# Acumulator.net
KiCad netlist of a schematic drawn in EAGLE
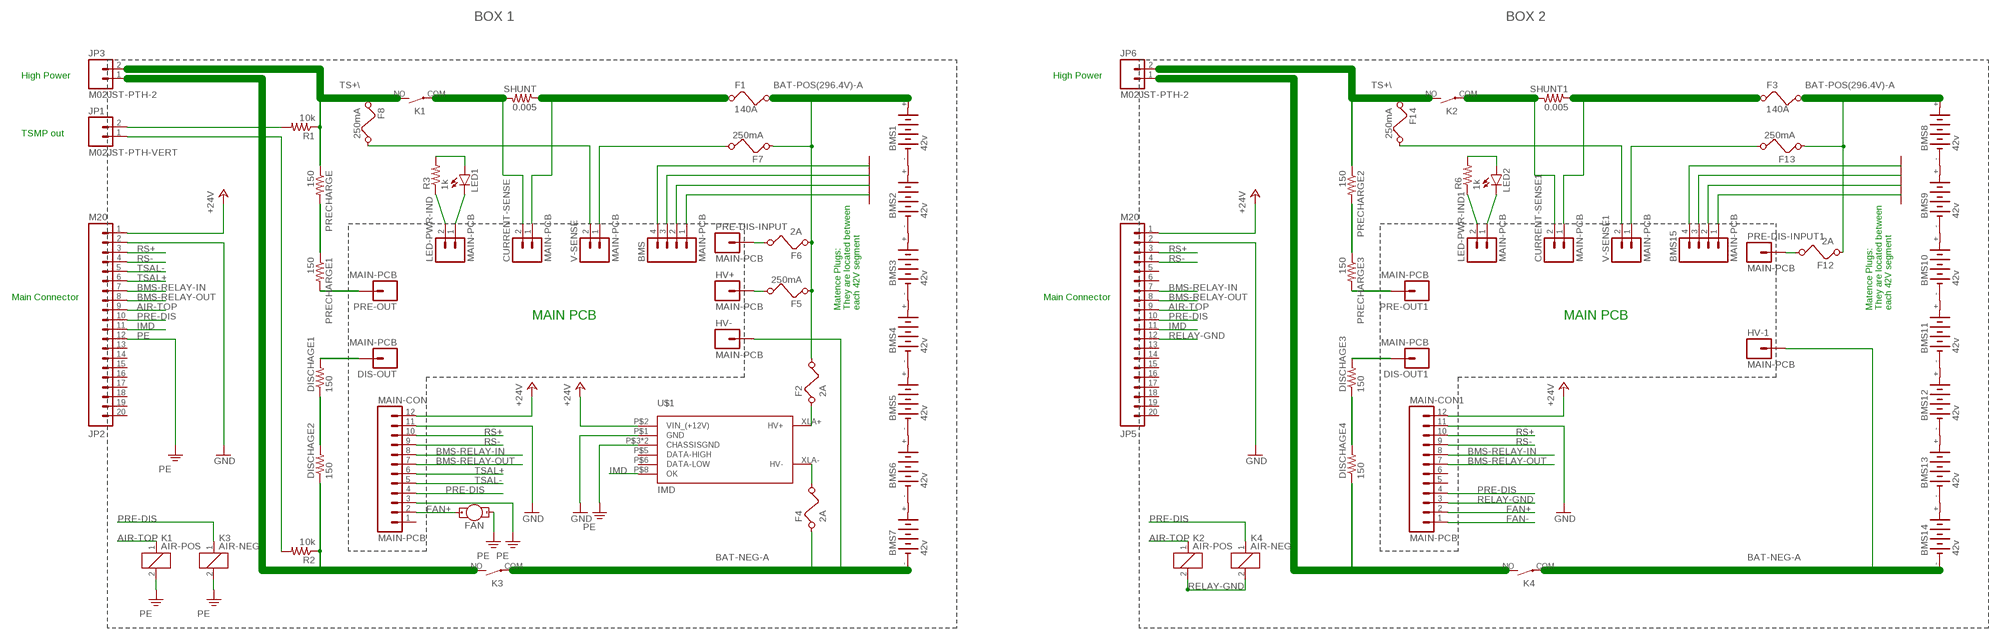
[diagram p0: schematic, sheet 1]
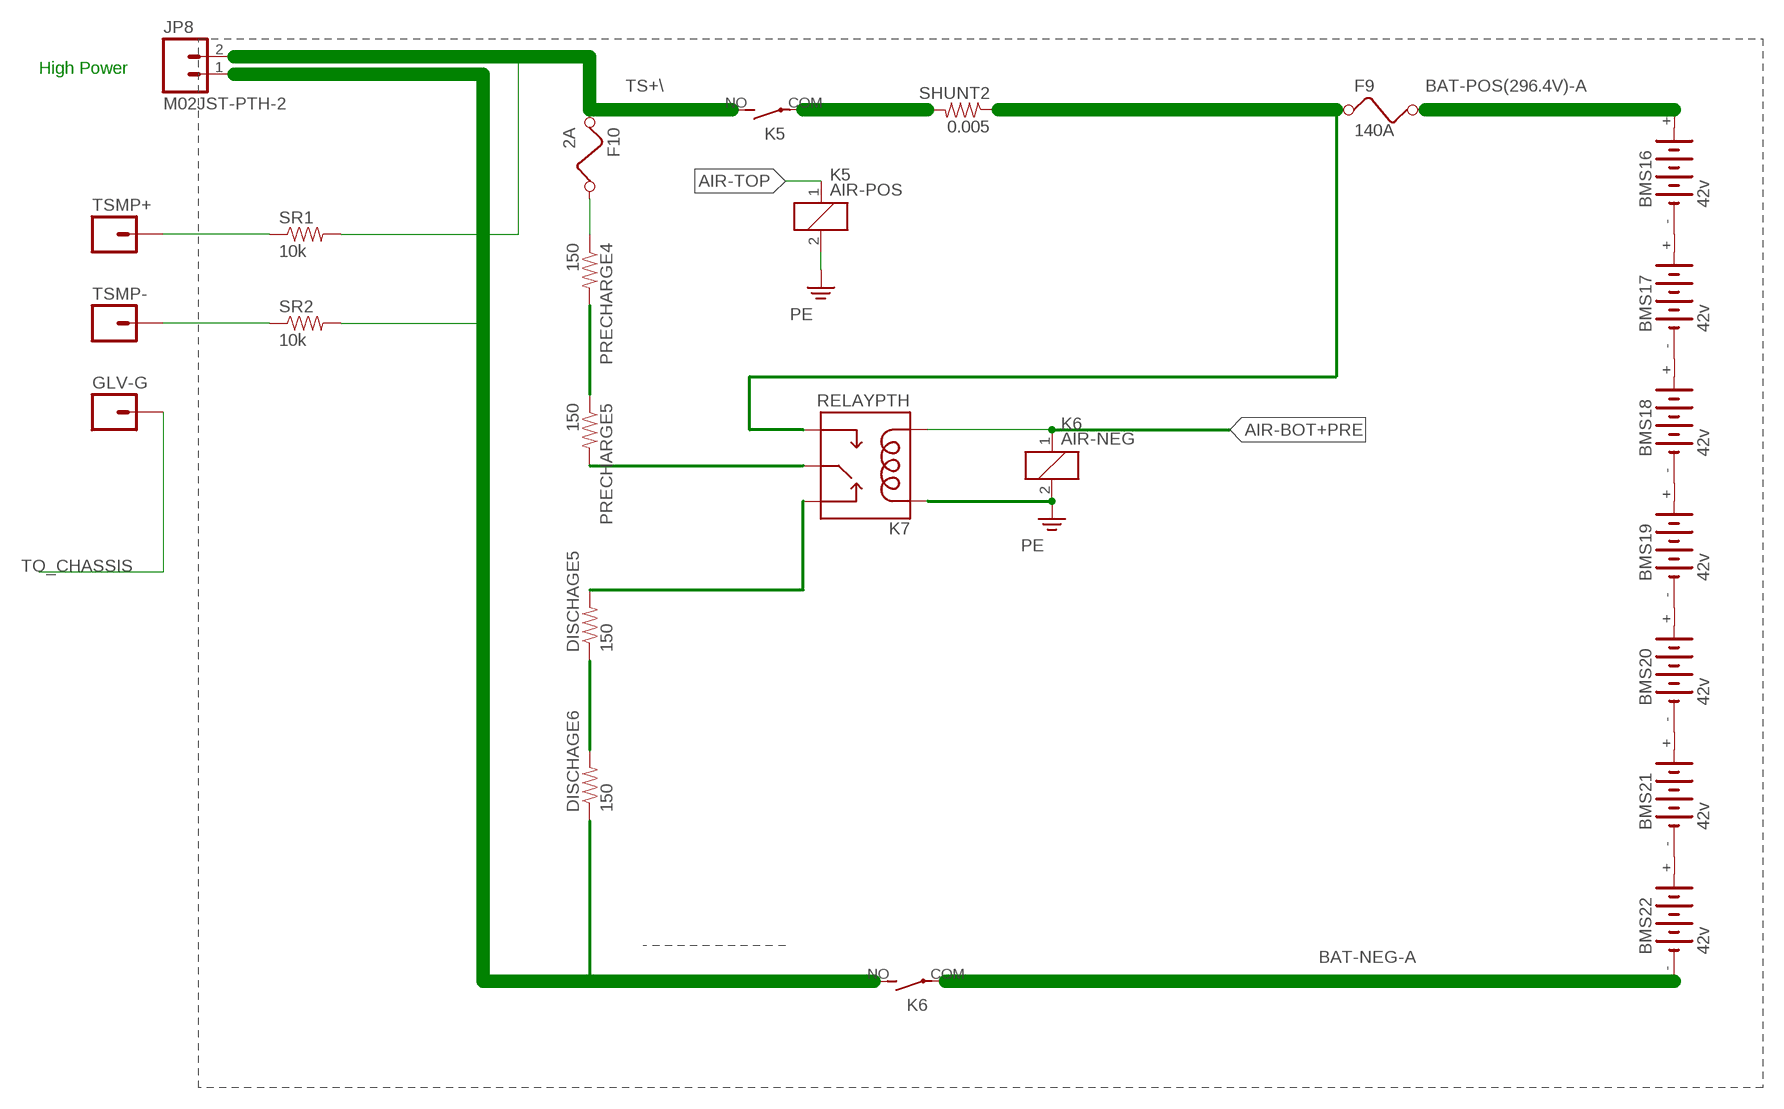
[diagram p1: schematic, sheet 2]
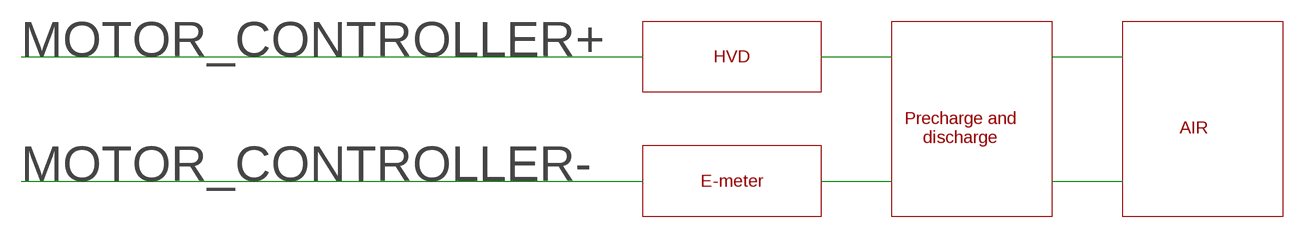
[diagram p2: schematic, sheet 3]

(export (version "E")
  (design (tool "Eeschema 10.0.6"))
  (components
    (comp (ref "BMS16")
      (value "42v")
      (footprint "eagle-import:VST4")
      (libsource (lib "eagle-import") (part "VST4V8"))
    )
    (comp (ref "BMS17")
      (value "42v")
      (footprint "eagle-import:VST4")
      (libsource (lib "eagle-import") (part "VST4V8"))
    )
    (comp (ref "BMS18")
      (value "42v")
      (footprint "eagle-import:VST4")
      (libsource (lib "eagle-import") (part "VST4V8"))
    )
    (comp (ref "BMS19")
      (value "42v")
      (footprint "eagle-import:VST4")
      (libsource (lib "eagle-import") (part "VST4V8"))
    )
    (comp (ref "BMS20")
      (value "42v")
      (footprint "eagle-import:VST4")
      (libsource (lib "eagle-import") (part "VST4V8"))
    )
    (comp (ref "BMS21")
      (value "42v")
      (footprint "eagle-import:VST4")
      (libsource (lib "eagle-import") (part "VST4V8"))
    )
    (comp (ref "BMS22")
      (value "42v")
      (footprint "eagle-import:VST4")
      (libsource (lib "eagle-import") (part "VST4V8"))
    )
    (comp (ref "DISCHAGE5")
      (value "150")
      (footprint "eagle-import:0603-RES")
      (libsource (lib "eagle-import") (part "2.0KOHM1/10W5%(0603)"))
    )
    (comp (ref "DISCHAGE6")
      (value "150")
      (footprint "eagle-import:0603-RES")
      (libsource (lib "eagle-import") (part "2.0KOHM1/10W5%(0603)"))
    )
    (comp (ref "F9")
      (value "140A")
      (footprint "eagle-import:FUSE")
      (libsource (lib "eagle-import") (part "FUSE"))
    )
    (comp (ref "F10")
      (value "2A")
      (footprint "eagle-import:FUSE")
      (libsource (lib "eagle-import") (part "FUSE"))
    )
    (comp (ref "GLV-G")
      (value "M01-SMTSO-256-ET")
      (footprint "eagle-import:SMTSO-256-ET")
      (libsource (lib "eagle-import") (part "M01-SMTSO-256-ET"))
    )
    (comp (ref "JP8")
      (value "M02JST-PTH-2")
      (footprint "eagle-import:JST-2-PTH")
      (libsource (lib "eagle-import") (part "M02JST-PTH-2"))
    )
    (comp (ref "K5")
      (value "AIR-POS")
      (footprint "eagle-import:APF30212A")
      (libsource (lib "eagle-import") (part "APF30212A"))
    )
    (comp (ref "K6")
      (value "AIR-NEG")
      (footprint "eagle-import:APF30212A")
      (libsource (lib "eagle-import") (part "APF30212A"))
    )
    (comp (ref "K7")
      (value "RELAYPTH")
      (footprint "eagle-import:RELAY-G5Q")
      (libsource (lib "eagle-import") (part "RELAYPTH"))
    )
    (comp (ref "PRECHARGE4")
      (value "150")
      (footprint "eagle-import:0603-RES")
      (libsource (lib "eagle-import") (part "2.0KOHM1/10W5%(0603)"))
    )
    (comp (ref "PRECHARGE5")
      (value "150")
      (footprint "eagle-import:0603-RES")
      (libsource (lib "eagle-import") (part "2.0KOHM1/10W5%(0603)"))
    )
    (comp (ref "SHUNT2")
      (value "0.005")
      (footprint "eagle-import:0603-RES")
      (libsource (lib "eagle-import") (part "2.0KOHM1/10W5%(0603)"))
    )
    (comp (ref "SR1")
      (value "10k")
      (footprint "eagle-import:0603-RES")
      (libsource (lib "eagle-import") (part "2.0KOHM1/10W5%(0603)"))
    )
    (comp (ref "SR2")
      (value "10k")
      (footprint "eagle-import:0603-RES")
      (libsource (lib "eagle-import") (part "2.0KOHM1/10W5%(0603)"))
    )
    (comp (ref "TSMP+")
      (value "M01-SMTSO-256-ET")
      (footprint "eagle-import:SMTSO-256-ET")
      (libsource (lib "eagle-import") (part "M01-SMTSO-256-ET"))
    )
    (comp (ref "TSMP-")
      (value "M01-SMTSO-256-ET")
      (footprint "eagle-import:SMTSO-256-ET")
      (libsource (lib "eagle-import") (part "M01-SMTSO-256-ET"))
    )
    (comp (ref "BMS")
      (value "MAIN-PCB")
      (footprint "eagle-import:1X04_LOCK_LONGPADS")
      (libsource (lib "eagle-import") (part "M04LOCK_LONGPADS"))
    )
    (comp (ref "BMS1")
      (value "42v")
      (footprint "eagle-import:VST4")
      (libsource (lib "eagle-import") (part "VST4V8"))
    )
    (comp (ref "BMS2")
      (value "42v")
      (footprint "eagle-import:VST4")
      (libsource (lib "eagle-import") (part "VST4V8"))
    )
    (comp (ref "BMS3")
      (value "42v")
      (footprint "eagle-import:VST4")
      (libsource (lib "eagle-import") (part "VST4V8"))
    )
    (comp (ref "BMS4")
      (value "42v")
      (footprint "eagle-import:VST4")
      (libsource (lib "eagle-import") (part "VST4V8"))
    )
    (comp (ref "BMS5")
      (value "42v")
      (footprint "eagle-import:VST4")
      (libsource (lib "eagle-import") (part "VST4V8"))
    )
    (comp (ref "BMS6")
      (value "42v")
      (footprint "eagle-import:VST4")
      (libsource (lib "eagle-import") (part "VST4V8"))
    )
    (comp (ref "BMS7")
      (value "42v")
      (footprint "eagle-import:VST4")
      (libsource (lib "eagle-import") (part "VST4V8"))
    )
    (comp (ref "BMS8")
      (value "42v")
      (footprint "eagle-import:VST4")
      (libsource (lib "eagle-import") (part "VST4V8"))
    )
    (comp (ref "BMS9")
      (value "42v")
      (footprint "eagle-import:VST4")
      (libsource (lib "eagle-import") (part "VST4V8"))
    )
    (comp (ref "BMS10")
      (value "42v")
      (footprint "eagle-import:VST4")
      (libsource (lib "eagle-import") (part "VST4V8"))
    )
    (comp (ref "BMS11")
      (value "42v")
      (footprint "eagle-import:VST4")
      (libsource (lib "eagle-import") (part "VST4V8"))
    )
    (comp (ref "BMS12")
      (value "42v")
      (footprint "eagle-import:VST4")
      (libsource (lib "eagle-import") (part "VST4V8"))
    )
    (comp (ref "BMS13")
      (value "42v")
      (footprint "eagle-import:VST4")
      (libsource (lib "eagle-import") (part "VST4V8"))
    )
    (comp (ref "BMS14")
      (value "42v")
      (footprint "eagle-import:VST4")
      (libsource (lib "eagle-import") (part "VST4V8"))
    )
    (comp (ref "BMS15")
      (value "MAIN-PCB")
      (footprint "eagle-import:1X04_LOCK_LONGPADS")
      (libsource (lib "eagle-import") (part "M04LOCK_LONGPADS"))
    )
    (comp (ref "CURRENT-SENSE")
      (value "MAIN-PCB")
      (footprint "eagle-import:JST-2-PTH-NS")
      (libsource (lib "eagle-import") (part "M02-JST-2-PTH-NO_SILK"))
    )
    (comp (ref "CURRENT-SENSE1")
      (value "MAIN-PCB")
      (footprint "eagle-import:JST-2-PTH-NS")
      (libsource (lib "eagle-import") (part "M02-JST-2-PTH-NO_SILK"))
    )
    (comp (ref "DIS-OUT")
      (value "MAIN-PCB")
      (footprint "eagle-import:1X01_OFFSET")
      (libsource (lib "eagle-import") (part "M01OFFSET"))
    )
    (comp (ref "DIS-OUT1")
      (value "MAIN-PCB")
      (footprint "eagle-import:1X01_OFFSET")
      (libsource (lib "eagle-import") (part "M01OFFSET"))
    )
    (comp (ref "DISCHAGE1")
      (value "150")
      (footprint "eagle-import:0603-RES")
      (libsource (lib "eagle-import") (part "2.0KOHM1/10W5%(0603)"))
    )
    (comp (ref "DISCHAGE2")
      (value "150")
      (footprint "eagle-import:0603-RES")
      (libsource (lib "eagle-import") (part "2.0KOHM1/10W5%(0603)"))
    )
    (comp (ref "DISCHAGE3")
      (value "150")
      (footprint "eagle-import:0603-RES")
      (libsource (lib "eagle-import") (part "2.0KOHM1/10W5%(0603)"))
    )
    (comp (ref "DISCHAGE4")
      (value "150")
      (footprint "eagle-import:0603-RES")
      (libsource (lib "eagle-import") (part "2.0KOHM1/10W5%(0603)"))
    )
    (comp (ref "F1")
      (value "140A")
      (footprint "eagle-import:FUSE")
      (libsource (lib "eagle-import") (part "FUSE"))
    )
    (comp (ref "F2")
      (value "2A")
      (footprint "eagle-import:FUSE")
      (libsource (lib "eagle-import") (part "FUSE"))
    )
    (comp (ref "F3")
      (value "140A")
      (footprint "eagle-import:FUSE")
      (libsource (lib "eagle-import") (part "FUSE"))
    )
    (comp (ref "F4")
      (value "2A")
      (footprint "eagle-import:FUSE")
      (libsource (lib "eagle-import") (part "FUSE"))
    )
    (comp (ref "F5")
      (value "250mA")
      (footprint "eagle-import:FUSE")
      (libsource (lib "eagle-import") (part "FUSE"))
    )
    (comp (ref "F6")
      (value "2A")
      (footprint "eagle-import:FUSE")
      (libsource (lib "eagle-import") (part "FUSE"))
    )
    (comp (ref "F7")
      (value "250mA")
      (footprint "eagle-import:FUSE")
      (libsource (lib "eagle-import") (part "FUSE"))
    )
    (comp (ref "F8")
      (value "250mA")
      (footprint "eagle-import:FUSE")
      (libsource (lib "eagle-import") (part "FUSE"))
    )
    (comp (ref "F12")
      (value "2A")
      (footprint "eagle-import:FUSE")
      (libsource (lib "eagle-import") (part "FUSE"))
    )
    (comp (ref "F13")
      (value "250mA")
      (footprint "eagle-import:FUSE")
      (libsource (lib "eagle-import") (part "FUSE"))
    )
    (comp (ref "F14")
      (value "250mA")
      (footprint "eagle-import:FUSE")
      (libsource (lib "eagle-import") (part "FUSE"))
    )
    (comp (ref "FAN")
      (value "MOTOR10MM")
      (footprint "eagle-import:VIBE-MOTOR-10MM")
      (libsource (lib "eagle-import") (part "MOTOR10MM"))
    )
    (comp (ref "HV+")
      (value "MAIN-PCB")
      (footprint "eagle-import:1X01_OFFSET")
      (libsource (lib "eagle-import") (part "M01OFFSET"))
    )
    (comp (ref "HV-")
      (value "MAIN-PCB")
      (footprint "eagle-import:1X01_OFFSET")
      (libsource (lib "eagle-import") (part "M01OFFSET"))
    )
    (comp (ref "HV-1")
      (value "MAIN-PCB")
      (footprint "eagle-import:1X01_OFFSET")
      (libsource (lib "eagle-import") (part "M01OFFSET"))
    )
    (comp (ref "JP1")
      (value "M02JST-PTH-VERT")
      (footprint "eagle-import:JST-2-PTH-VERT")
      (libsource (lib "eagle-import") (part "M02JST-PTH-VERT"))
    )
    (comp (ref "JP2")
      (value "M20")
      (footprint "eagle-import:1X20")
      (libsource (lib "eagle-import") (part "M20"))
    )
    (comp (ref "JP3")
      (value "M02JST-PTH-2")
      (footprint "eagle-import:JST-2-PTH")
      (libsource (lib "eagle-import") (part "M02JST-PTH-2"))
    )
    (comp (ref "JP5")
      (value "M20")
      (footprint "eagle-import:1X20")
      (libsource (lib "eagle-import") (part "M20"))
    )
    (comp (ref "JP6")
      (value "M02JST-PTH-2")
      (footprint "eagle-import:JST-2-PTH")
      (libsource (lib "eagle-import") (part "M02JST-PTH-2"))
    )
    (comp (ref "K1")
      (value "AIR-POS")
      (footprint "eagle-import:APF30212A")
      (libsource (lib "eagle-import") (part "APF30212A"))
    )
    (comp (ref "K2")
      (value "AIR-POS")
      (footprint "eagle-import:APF30212A")
      (libsource (lib "eagle-import") (part "APF30212A"))
    )
    (comp (ref "K3")
      (value "AIR-NEG")
      (footprint "eagle-import:APF30212A")
      (libsource (lib "eagle-import") (part "APF30212A"))
    )
    (comp (ref "K4")
      (value "AIR-NEG")
      (footprint "eagle-import:APF30212A")
      (libsource (lib "eagle-import") (part "APF30212A"))
    )
    (comp (ref "LED-PWR-IND")
      (value "MAIN-PCB")
      (footprint "eagle-import:JST-2-PTH-NS")
      (libsource (lib "eagle-import") (part "M02-JST-2-PTH-NO_SILK"))
    )
    (comp (ref "LED-PWR-IND1")
      (value "MAIN-PCB")
      (footprint "eagle-import:JST-2-PTH-NS")
      (libsource (lib "eagle-import") (part "M02-JST-2-PTH-NO_SILK"))
    )
    (comp (ref "LED1")
      (value "LED5MM")
      (footprint "eagle-import:LED5MM")
      (libsource (lib "eagle-import") (part "LED5MM"))
    )
    (comp (ref "LED2")
      (value "LED5MM")
      (footprint "eagle-import:LED5MM")
      (libsource (lib "eagle-import") (part "LED5MM"))
    )
    (comp (ref "MAIN-CON")
      (value "MAIN-PCB")
      (footprint "eagle-import:1X12_LOCK")
      (libsource (lib "eagle-import") (part "M12LOCK"))
    )
    (comp (ref "MAIN-CON1")
      (value "MAIN-PCB")
      (footprint "eagle-import:1X12_LOCK")
      (libsource (lib "eagle-import") (part "M12LOCK"))
    )
    (comp (ref "PRE-DIS-INPUT")
      (value "MAIN-PCB")
      (footprint "eagle-import:1X01_OFFSET")
      (libsource (lib "eagle-import") (part "M01OFFSET"))
    )
    (comp (ref "PRE-DIS-INPUT1")
      (value "MAIN-PCB")
      (footprint "eagle-import:1X01_OFFSET")
      (libsource (lib "eagle-import") (part "M01OFFSET"))
    )
    (comp (ref "PRE-OUT")
      (value "MAIN-PCB")
      (footprint "eagle-import:1X01_OFFSET")
      (libsource (lib "eagle-import") (part "M01OFFSET"))
    )
    (comp (ref "PRE-OUT1")
      (value "MAIN-PCB")
      (footprint "eagle-import:1X01_OFFSET")
      (libsource (lib "eagle-import") (part "M01OFFSET"))
    )
    (comp (ref "PRECHARGE")
      (value "150")
      (footprint "eagle-import:0603-RES")
      (libsource (lib "eagle-import") (part "2.0KOHM1/10W5%(0603)"))
    )
    (comp (ref "PRECHARGE1")
      (value "150")
      (footprint "eagle-import:0603-RES")
      (libsource (lib "eagle-import") (part "2.0KOHM1/10W5%(0603)"))
    )
    (comp (ref "PRECHARGE2")
      (value "150")
      (footprint "eagle-import:0603-RES")
      (libsource (lib "eagle-import") (part "2.0KOHM1/10W5%(0603)"))
    )
    (comp (ref "PRECHARGE3")
      (value "150")
      (footprint "eagle-import:0603-RES")
      (libsource (lib "eagle-import") (part "2.0KOHM1/10W5%(0603)"))
    )
    (comp (ref "R1")
      (value "10k")
      (footprint "eagle-import:0805")
      (libsource (lib "eagle-import") (part "RESISTOR0805-RES"))
    )
    (comp (ref "R2")
      (value "10k")
      (footprint "eagle-import:0805")
      (libsource (lib "eagle-import") (part "RESISTOR0805-RES"))
    )
    (comp (ref "R3")
      (value "1k")
      (footprint "eagle-import:0603-RES")
      (libsource (lib "eagle-import") (part "2.0KOHM1/10W5%(0603)"))
    )
    (comp (ref "R6")
      (value "1k")
      (footprint "eagle-import:0603-RES")
      (libsource (lib "eagle-import") (part "2.0KOHM1/10W5%(0603)"))
    )
    (comp (ref "SHUNT")
      (value "0.005")
      (footprint "eagle-import:0603-RES")
      (libsource (lib "eagle-import") (part "2.0KOHM1/10W5%(0603)"))
    )
    (comp (ref "SHUNT1")
      (value "0.005")
      (footprint "eagle-import:0603-RES")
      (libsource (lib "eagle-import") (part "2.0KOHM1/10W5%(0603)"))
    )
    (comp (ref "U$1")
      (value "IMD")
      (footprint "eagle-import:IMD")
      (libsource (lib "eagle-import") (part "IMD"))
    )
    (comp (ref "V-SENSE")
      (value "MAIN-PCB")
      (footprint "eagle-import:JST-2-PTH-NS")
      (libsource (lib "eagle-import") (part "M02-JST-2-PTH-NO_SILK"))
    )
    (comp (ref "V-SENSE1")
      (value "MAIN-PCB")
      (footprint "eagle-import:JST-2-PTH-NS")
      (libsource (lib "eagle-import") (part "M02-JST-2-PTH-NO_SILK"))
    )
  )
  (nets
    (net (code "1") (name "+24V") (class "Default")
      (node (ref "JP2") (pin "1") (pinfunction "1_1") (pintype "passive"))
      (node (ref "JP5") (pin "1") (pinfunction "1_1") (pintype "passive"))
      (node (ref "MAIN-CON") (pin "12") (pinfunction "12_12") (pintype "passive"))
      (node (ref "MAIN-CON1") (pin "12") (pinfunction "12_12") (pintype "passive"))
      (node (ref "U$1") (pin "P$2") (pinfunction "VIN_(+12V)_P$2") (pintype "bidirectional"))
    )
    (net (code "2") (name "AIR-BOT+PRE") (class "Default")
      (node (ref "K6") (pin "1") (pinfunction "1_1") (pintype "passive"))
      (node (ref "K7") (pin "1") (pinfunction "COIL2_1") (pintype "bidirectional"))
    )
    (net (code "3") (name "AIR-TOP") (class "Default")
      (node (ref "JP2") (pin "9") (pinfunction "9_9") (pintype "passive"))
      (node (ref "JP5") (pin "9") (pinfunction "9_9") (pintype "passive"))
      (node (ref "K1") (pin "1") (pinfunction "1_1") (pintype "passive"))
      (node (ref "K2") (pin "1") (pinfunction "1_1") (pintype "passive"))
      (node (ref "K5") (pin "1") (pinfunction "1_1") (pintype "passive"))
    )
    (net (code "4") (name "BAT-NEG-A") (class "Default")
      (node (ref "BMS14") (pin "-") (pinfunction "-_-") (pintype "passive"))
      (node (ref "BMS22") (pin "-") (pinfunction "-_-") (pintype "passive"))
      (node (ref "BMS7") (pin "-") (pinfunction "-_-") (pintype "passive"))
      (node (ref "F4") (pin "1") (pinfunction "1_1") (pintype "passive"))
      (node (ref "HV-") (pin "1") (pinfunction "1_1") (pintype "passive"))
      (node (ref "HV-1") (pin "1") (pinfunction "1_1") (pintype "passive"))
      (node (ref "K3") (pin "COM") (pinfunction "P_COM") (pintype "passive"))
      (node (ref "K4") (pin "COM") (pinfunction "P_COM") (pintype "passive"))
      (node (ref "K6") (pin "COM") (pinfunction "P_COM") (pintype "passive"))
    )
    (net (code "5") (name "BAT-POS(296.4V)-A") (class "Default")
      (node (ref "BMS1") (pin "+") (pinfunction "+_+") (pintype "passive"))
      (node (ref "BMS16") (pin "+") (pinfunction "+_+") (pintype "passive"))
      (node (ref "BMS8") (pin "+") (pinfunction "+_+") (pintype "passive"))
      (node (ref "F1") (pin "2") (pinfunction "2_2") (pintype "passive"))
      (node (ref "F12") (pin "1") (pinfunction "1_1") (pintype "passive"))
      (node (ref "F13") (pin "1") (pinfunction "1_1") (pintype "passive"))
      (node (ref "F2") (pin "2") (pinfunction "2_2") (pintype "passive"))
      (node (ref "F3") (pin "2") (pinfunction "2_2") (pintype "passive"))
      (node (ref "F5") (pin "1") (pinfunction "1_1") (pintype "passive"))
      (node (ref "F6") (pin "1") (pinfunction "1_1") (pintype "passive"))
      (node (ref "F7") (pin "1") (pinfunction "1_1") (pintype "passive"))
      (node (ref "F9") (pin "2") (pinfunction "2_2") (pintype "passive"))
    )
    (net (code "6") (name "BMS-RELAY-IN") (class "Default")
      (node (ref "JP2") (pin "7") (pinfunction "7_7") (pintype "passive"))
      (node (ref "JP5") (pin "7") (pinfunction "7_7") (pintype "passive"))
      (node (ref "MAIN-CON") (pin "8") (pinfunction "8_8") (pintype "passive"))
      (node (ref "MAIN-CON1") (pin "8") (pinfunction "8_8") (pintype "passive"))
    )
    (net (code "7") (name "BMS-RELAY-OUT") (class "Default")
      (node (ref "JP2") (pin "8") (pinfunction "8_8") (pintype "passive"))
      (node (ref "JP5") (pin "8") (pinfunction "8_8") (pintype "passive"))
      (node (ref "MAIN-CON") (pin "7") (pinfunction "7_7") (pintype "passive"))
      (node (ref "MAIN-CON1") (pin "7") (pinfunction "7_7") (pintype "passive"))
    )
    (net (code "8") (name "FAN+") (class "Default")
      (node (ref "FAN") (pin "+") (pinfunction "+_+") (pintype "bidirectional"))
      (node (ref "MAIN-CON") (pin "2") (pinfunction "2_2") (pintype "passive"))
      (node (ref "MAIN-CON1") (pin "2") (pinfunction "2_2") (pintype "passive"))
    )
    (net (code "9") (name "FAN-") (class "Default")
      (node (ref "MAIN-CON1") (pin "1") (pinfunction "1_1") (pintype "passive"))
    )
    (net (code "10") (name "GND") (class "Default")
      (node (ref "JP2") (pin "2") (pinfunction "2_2") (pintype "passive"))
      (node (ref "JP5") (pin "2") (pinfunction "2_2") (pintype "passive"))
      (node (ref "MAIN-CON") (pin "11") (pinfunction "11_11") (pintype "passive"))
      (node (ref "MAIN-CON1") (pin "11") (pinfunction "11_11") (pintype "passive"))
      (node (ref "U$1") (pin "P$1") (pinfunction "GND_P$1") (pintype "bidirectional"))
    )
    (net (code "11") (name "IMD") (class "Default")
      (node (ref "JP2") (pin "11") (pinfunction "11_11") (pintype "passive"))
      (node (ref "JP5") (pin "11") (pinfunction "11_11") (pintype "passive"))
      (node (ref "U$1") (pin "P$8") (pinfunction "OK_P$8") (pintype "bidirectional"))
    )
    (net (code "14") (name "Net-(BMS1-Pad-)") (class "Default")
      (node (ref "BMS1") (pin "-") (pinfunction "-_-") (pintype "passive"))
      (node (ref "BMS2") (pin "+") (pinfunction "+_+") (pintype "passive"))
    )
    (net (code "15") (name "Net-(BMS2-Pad-)") (class "Default")
      (node (ref "BMS2") (pin "-") (pinfunction "-_-") (pintype "passive"))
      (node (ref "BMS3") (pin "+") (pinfunction "+_+") (pintype "passive"))
    )
    (net (code "16") (name "Net-(BMS3-Pad-)") (class "Default")
      (node (ref "BMS3") (pin "-") (pinfunction "-_-") (pintype "passive"))
      (node (ref "BMS4") (pin "+") (pinfunction "+_+") (pintype "passive"))
    )
    (net (code "17") (name "Net-(BMS4-Pad-)") (class "Default")
      (node (ref "BMS4") (pin "-") (pinfunction "-_-") (pintype "passive"))
      (node (ref "BMS5") (pin "+") (pinfunction "+_+") (pintype "passive"))
    )
    (net (code "18") (name "Net-(BMS5-Pad-)") (class "Default")
      (node (ref "BMS5") (pin "-") (pinfunction "-_-") (pintype "passive"))
      (node (ref "BMS6") (pin "+") (pinfunction "+_+") (pintype "passive"))
    )
    (net (code "19") (name "Net-(BMS6-Pad-)") (class "Default")
      (node (ref "BMS6") (pin "-") (pinfunction "-_-") (pintype "passive"))
      (node (ref "BMS7") (pin "+") (pinfunction "+_+") (pintype "passive"))
    )
    (net (code "20") (name "Net-(BMS8-Pad-)") (class "Default")
      (node (ref "BMS8") (pin "-") (pinfunction "-_-") (pintype "passive"))
      (node (ref "BMS9") (pin "+") (pinfunction "+_+") (pintype "passive"))
    )
    (net (code "21") (name "Net-(BMS10-Pad+)") (class "Default")
      (node (ref "BMS10") (pin "+") (pinfunction "+_+") (pintype "passive"))
      (node (ref "BMS9") (pin "-") (pinfunction "-_-") (pintype "passive"))
    )
    (net (code "22") (name "Net-(BMS10-Pad-)") (class "Default")
      (node (ref "BMS10") (pin "-") (pinfunction "-_-") (pintype "passive"))
      (node (ref "BMS11") (pin "+") (pinfunction "+_+") (pintype "passive"))
    )
    (net (code "23") (name "Net-(BMS11-Pad-)") (class "Default")
      (node (ref "BMS11") (pin "-") (pinfunction "-_-") (pintype "passive"))
      (node (ref "BMS12") (pin "+") (pinfunction "+_+") (pintype "passive"))
    )
    (net (code "24") (name "Net-(BMS12-Pad-)") (class "Default")
      (node (ref "BMS12") (pin "-") (pinfunction "-_-") (pintype "passive"))
      (node (ref "BMS13") (pin "+") (pinfunction "+_+") (pintype "passive"))
    )
    (net (code "25") (name "Net-(BMS13-Pad-)") (class "Default")
      (node (ref "BMS13") (pin "-") (pinfunction "-_-") (pintype "passive"))
      (node (ref "BMS14") (pin "+") (pinfunction "+_+") (pintype "passive"))
    )
    (net (code "26") (name "Net-(BMS16-Pad-)") (class "Default")
      (node (ref "BMS16") (pin "-") (pinfunction "-_-") (pintype "passive"))
      (node (ref "BMS17") (pin "+") (pinfunction "+_+") (pintype "passive"))
    )
    (net (code "27") (name "Net-(BMS17-Pad-)") (class "Default")
      (node (ref "BMS17") (pin "-") (pinfunction "-_-") (pintype "passive"))
      (node (ref "BMS18") (pin "+") (pinfunction "+_+") (pintype "passive"))
    )
    (net (code "28") (name "Net-(BMS18-Pad-)") (class "Default")
      (node (ref "BMS18") (pin "-") (pinfunction "-_-") (pintype "passive"))
      (node (ref "BMS19") (pin "+") (pinfunction "+_+") (pintype "passive"))
    )
    (net (code "29") (name "Net-(BMS19-Pad-)") (class "Default")
      (node (ref "BMS19") (pin "-") (pinfunction "-_-") (pintype "passive"))
      (node (ref "BMS20") (pin "+") (pinfunction "+_+") (pintype "passive"))
    )
    (net (code "30") (name "Net-(BMS20-Pad-)") (class "Default")
      (node (ref "BMS20") (pin "-") (pinfunction "-_-") (pintype "passive"))
      (node (ref "BMS21") (pin "+") (pinfunction "+_+") (pintype "passive"))
    )
    (net (code "31") (name "Net-(BMS21-Pad-)") (class "Default")
      (node (ref "BMS21") (pin "-") (pinfunction "-_-") (pintype "passive"))
      (node (ref "BMS22") (pin "+") (pinfunction "+_+") (pintype "passive"))
    )
    (net (code "32") (name "Net-(CURRENT-SENSE-Pad1)") (class "Default")
      (node (ref "CURRENT-SENSE") (pin "1") (pinfunction "1_1") (pintype "passive"))
      (node (ref "F1") (pin "1") (pinfunction "1_1") (pintype "passive"))
      (node (ref "SHUNT") (pin "1") (pinfunction "1_1") (pintype "passive"))
    )
    (net (code "33") (name "Net-(CURRENT-SENSE1-Pad1)") (class "Default")
      (node (ref "CURRENT-SENSE1") (pin "1") (pinfunction "1_1") (pintype "passive"))
      (node (ref "F3") (pin "1") (pinfunction "1_1") (pintype "passive"))
      (node (ref "SHUNT1") (pin "1") (pinfunction "1_1") (pintype "passive"))
    )
    (net (code "34") (name "Net-(DIS-OUT-Pad1)") (class "Default")
      (node (ref "DIS-OUT") (pin "1") (pinfunction "1_1") (pintype "passive"))
      (node (ref "DISCHAGE1") (pin "2") (pinfunction "2_2") (pintype "passive"))
    )
    (net (code "35") (name "Net-(DIS-OUT1-Pad1)") (class "Default")
      (node (ref "DIS-OUT1") (pin "1") (pinfunction "1_1") (pintype "passive"))
      (node (ref "DISCHAGE3") (pin "2") (pinfunction "2_2") (pintype "passive"))
    )
    (net (code "36") (name "Net-(DISCHAGE1-Pad1)") (class "Default")
      (node (ref "DISCHAGE1") (pin "1") (pinfunction "1_1") (pintype "passive"))
      (node (ref "DISCHAGE2") (pin "2") (pinfunction "2_2") (pintype "passive"))
    )
    (net (code "37") (name "Net-(DISCHAGE3-Pad1)") (class "Default")
      (node (ref "DISCHAGE3") (pin "1") (pinfunction "1_1") (pintype "passive"))
      (node (ref "DISCHAGE4") (pin "2") (pinfunction "2_2") (pintype "passive"))
    )
    (net (code "38") (name "Net-(DISCHAGE5-Pad1)") (class "Default")
      (node (ref "DISCHAGE5") (pin "1") (pinfunction "1_1") (pintype "passive"))
      (node (ref "DISCHAGE6") (pin "2") (pinfunction "2_2") (pintype "passive"))
    )
    (net (code "39") (name "Net-(F5-Pad2)") (class "Default")
      (node (ref "F5") (pin "2") (pinfunction "2_2") (pintype "passive"))
      (node (ref "HV+") (pin "1") (pinfunction "1_1") (pintype "passive"))
    )
    (net (code "40") (name "Net-(F6-Pad2)") (class "Default")
      (node (ref "F6") (pin "2") (pinfunction "2_2") (pintype "passive"))
      (node (ref "PRE-DIS-INPUT") (pin "1") (pinfunction "1_1") (pintype "passive"))
    )
    (net (code "41") (name "Net-(F7-Pad2)") (class "Default")
      (node (ref "F7") (pin "2") (pinfunction "2_2") (pintype "passive"))
      (node (ref "V-SENSE") (pin "1") (pinfunction "1_1") (pintype "passive"))
    )
    (net (code "42") (name "Net-(F8-Pad2)") (class "Default")
      (node (ref "F8") (pin "2") (pinfunction "2_2") (pintype "passive"))
      (node (ref "V-SENSE") (pin "2") (pinfunction "2_2") (pintype "passive"))
    )
    (net (code "43") (name "Net-(F10-Pad2)") (class "Default")
      (node (ref "F10") (pin "2") (pinfunction "2_2") (pintype "passive"))
      (node (ref "PRECHARGE4") (pin "1") (pinfunction "1_1") (pintype "passive"))
    )
    (net (code "44") (name "Net-(F12-Pad2)") (class "Default")
      (node (ref "F12") (pin "2") (pinfunction "2_2") (pintype "passive"))
      (node (ref "PRE-DIS-INPUT1") (pin "1") (pinfunction "1_1") (pintype "passive"))
    )
    (net (code "45") (name "Net-(F13-Pad2)") (class "Default")
      (node (ref "F13") (pin "2") (pinfunction "2_2") (pintype "passive"))
      (node (ref "V-SENSE1") (pin "1") (pinfunction "1_1") (pintype "passive"))
    )
    (net (code "46") (name "Net-(F14-Pad2)") (class "Default")
      (node (ref "F14") (pin "2") (pinfunction "2_2") (pintype "passive"))
      (node (ref "V-SENSE1") (pin "2") (pinfunction "2_2") (pintype "passive"))
    )
    (net (code "47") (name "Net-(JP1-Pad1)") (class "Default")
      (node (ref "JP1") (pin "1") (pinfunction "1_1") (pintype "passive"))
      (node (ref "R2") (pin "2") (pinfunction "2_2") (pintype "passive"))
    )
    (net (code "48") (name "Net-(JP1-Pad2)") (class "Default")
      (node (ref "JP1") (pin "2") (pinfunction "2_2") (pintype "passive"))
      (node (ref "R1") (pin "2") (pinfunction "2_2") (pintype "passive"))
    )
    (net (code "49") (name "Net-(K1B-P)") (class "Default")
      (node (ref "CURRENT-SENSE") (pin "2") (pinfunction "2_2") (pintype "passive"))
      (node (ref "K1") (pin "COM") (pinfunction "P_COM") (pintype "passive"))
      (node (ref "SHUNT") (pin "2") (pinfunction "2_2") (pintype "passive"))
    )
    (net (code "50") (name "Net-(K2B-P)") (class "Default")
      (node (ref "CURRENT-SENSE1") (pin "2") (pinfunction "2_2") (pintype "passive"))
      (node (ref "K2") (pin "COM") (pinfunction "P_COM") (pintype "passive"))
      (node (ref "SHUNT1") (pin "2") (pinfunction "2_2") (pintype "passive"))
    )
    (net (code "51") (name "Net-(K3B-S)") (class "Default")
      (node (ref "DISCHAGE2") (pin "1") (pinfunction "1_1") (pintype "passive"))
      (node (ref "JP3") (pin "1") (pinfunction "1_1") (pintype "passive"))
      (node (ref "K3") (pin "NO") (pinfunction "S_NO") (pintype "passive"))
      (node (ref "R2") (pin "1") (pinfunction "1_1") (pintype "passive"))
    )
    (net (code "52") (name "Net-(K4B-S)") (class "Default")
      (node (ref "DISCHAGE4") (pin "1") (pinfunction "1_1") (pintype "passive"))
      (node (ref "JP6") (pin "1") (pinfunction "1_1") (pintype "passive"))
      (node (ref "K4") (pin "NO") (pinfunction "S_NO") (pintype "passive"))
    )
    (net (code "53") (name "Net-(K5B-P)") (class "Default")
      (node (ref "K5") (pin "COM") (pinfunction "P_COM") (pintype "passive"))
      (node (ref "SHUNT2") (pin "2") (pinfunction "2_2") (pintype "passive"))
    )
    (net (code "54") (name "Net-(K6B-S)") (class "Default")
      (node (ref "DISCHAGE6") (pin "1") (pinfunction "1_1") (pintype "passive"))
      (node (ref "JP8") (pin "1") (pinfunction "1_1") (pintype "passive"))
      (node (ref "K6") (pin "NO") (pinfunction "S_NO") (pintype "passive"))
      (node (ref "SR2") (pin "2") (pinfunction "2_2") (pintype "passive"))
    )
    (net (code "55") (name "Net-(K7-MAIN)") (class "Default")
      (node (ref "K7") (pin "2") (pinfunction "MAIN_2") (pintype "bidirectional"))
      (node (ref "PRECHARGE5") (pin "2") (pinfunction "2_2") (pintype "passive"))
    )
    (net (code "56") (name "Net-(K7-NC)") (class "Default")
      (node (ref "DISCHAGE5") (pin "2") (pinfunction "2_2") (pintype "passive"))
      (node (ref "K7") (pin "4") (pinfunction "NC_4") (pintype "bidirectional"))
    )
    (net (code "57") (name "Net-(K7-NO)") (class "Default")
      (node (ref "F9") (pin "1") (pinfunction "1_1") (pintype "passive"))
      (node (ref "K7") (pin "3") (pinfunction "NO_3") (pintype "bidirectional"))
      (node (ref "SHUNT2") (pin "1") (pinfunction "1_1") (pintype "passive"))
    )
    (net (code "58") (name "Net-(LED-PWR-IND-Pad2)") (class "Default")
      (node (ref "LED-PWR-IND") (pin "2") (pinfunction "2_2") (pintype "passive"))
      (node (ref "R3") (pin "1") (pinfunction "1_1") (pintype "passive"))
    )
    (net (code "59") (name "Net-(LED-PWR-IND1-Pad2)") (class "Default")
      (node (ref "LED-PWR-IND1") (pin "2") (pinfunction "2_2") (pintype "passive"))
      (node (ref "R6") (pin "1") (pinfunction "1_1") (pintype "passive"))
    )
    (net (code "60") (name "Net-(LED1-C)") (class "Default")
      (node (ref "LED-PWR-IND") (pin "1") (pinfunction "1_1") (pintype "passive"))
      (node (ref "LED1") (pin "K") (pinfunction "C_K") (pintype "passive"))
    )
    (net (code "61") (name "Net-(LED1-PadA)") (class "Default")
      (node (ref "LED1") (pin "A") (pinfunction "A_A") (pintype "passive"))
      (node (ref "R3") (pin "2") (pinfunction "2_2") (pintype "passive"))
    )
    (net (code "62") (name "Net-(LED2-C)") (class "Default")
      (node (ref "LED-PWR-IND1") (pin "1") (pinfunction "1_1") (pintype "passive"))
      (node (ref "LED2") (pin "K") (pinfunction "C_K") (pintype "passive"))
    )
    (net (code "63") (name "Net-(LED2-PadA)") (class "Default")
      (node (ref "LED2") (pin "A") (pinfunction "A_A") (pintype "passive"))
      (node (ref "R6") (pin "2") (pinfunction "2_2") (pintype "passive"))
    )
    (net (code "64") (name "Net-(PRE-OUT-Pad1)") (class "Default")
      (node (ref "PRE-OUT") (pin "1") (pinfunction "1_1") (pintype "passive"))
      (node (ref "PRECHARGE1") (pin "2") (pinfunction "2_2") (pintype "passive"))
    )
    (net (code "65") (name "Net-(PRE-OUT1-Pad1)") (class "Default")
      (node (ref "PRE-OUT1") (pin "1") (pinfunction "1_1") (pintype "passive"))
      (node (ref "PRECHARGE3") (pin "2") (pinfunction "2_2") (pintype "passive"))
    )
    (net (code "66") (name "Net-(PRECHARGE-Pad2)") (class "Default")
      (node (ref "PRECHARGE") (pin "2") (pinfunction "2_2") (pintype "passive"))
      (node (ref "PRECHARGE1") (pin "1") (pinfunction "1_1") (pintype "passive"))
    )
    (net (code "67") (name "Net-(PRECHARGE2-Pad2)") (class "Default")
      (node (ref "PRECHARGE2") (pin "2") (pinfunction "2_2") (pintype "passive"))
      (node (ref "PRECHARGE3") (pin "1") (pinfunction "1_1") (pintype "passive"))
    )
    (net (code "68") (name "Net-(PRECHARGE4-Pad2)") (class "Default")
      (node (ref "PRECHARGE4") (pin "2") (pinfunction "2_2") (pintype "passive"))
      (node (ref "PRECHARGE5") (pin "1") (pinfunction "1_1") (pintype "passive"))
    )
    (net (code "69") (name "Net-(TSMP+-1)") (class "Default")
      (node (ref "SR1") (pin "1") (pinfunction "1_1") (pintype "passive"))
      (node (ref "TSMP+") (pin "P$1") (pinfunction "1_P$1") (pintype "passive"))
    )
    (net (code "70") (name "Net-(TSMP--1)") (class "Default")
      (node (ref "SR2") (pin "1") (pinfunction "1_1") (pintype "passive"))
      (node (ref "TSMP-") (pin "P$1") (pinfunction "1_P$1") (pintype "passive"))
    )
    (net (code "71") (name "Net-(U$1-HV+)") (class "Default")
      (node (ref "F2") (pin "1") (pinfunction "1_1") (pintype "passive"))
      (node (ref "U$1") (pin "XLA+") (pinfunction "HV+_XLA+") (pintype "bidirectional"))
    )
    (net (code "72") (name "Net-(U$1-HV-)") (class "Default")
      (node (ref "F4") (pin "2") (pinfunction "2_2") (pintype "passive"))
      (node (ref "U$1") (pin "XLA-") (pinfunction "HV-_XLA-") (pintype "bidirectional"))
    )
    (net (code "73") (name "PE") (class "Default")
      (node (ref "FAN") (pin "-") (pinfunction "-_-") (pintype "bidirectional"))
      (node (ref "JP2") (pin "12") (pinfunction "12_12") (pintype "passive"))
      (node (ref "K1") (pin "2") (pinfunction "2_2") (pintype "passive"))
      (node (ref "K3") (pin "2") (pinfunction "2_2") (pintype "passive"))
      (node (ref "K5") (pin "2") (pinfunction "2_2") (pintype "passive"))
      (node (ref "K6") (pin "2") (pinfunction "2_2") (pintype "passive"))
      (node (ref "K7") (pin "5") (pinfunction "COIL1_5") (pintype "bidirectional"))
      (node (ref "MAIN-CON") (pin "3") (pinfunction "3_3") (pintype "passive"))
      (node (ref "U$1") (pin "P$3") (pinfunction "CHASSISGND_P$3") (pintype "bidirectional"))
      (node (ref "U$1") (pin "P$4") (pinfunction "CHASSISGND_P$4") (pintype "bidirectional"))
    )
    (net (code "74") (name "PRE-DIS") (class "Default")
      (node (ref "JP2") (pin "10") (pinfunction "10_10") (pintype "passive"))
      (node (ref "JP5") (pin "10") (pinfunction "10_10") (pintype "passive"))
      (node (ref "K3") (pin "1") (pinfunction "1_1") (pintype "passive"))
      (node (ref "K4") (pin "1") (pinfunction "1_1") (pintype "passive"))
      (node (ref "MAIN-CON") (pin "4") (pinfunction "4_4") (pintype "passive"))
      (node (ref "MAIN-CON1") (pin "4") (pinfunction "4_4") (pintype "passive"))
    )
    (net (code "75") (name "RELAY-GND") (class "Default")
      (node (ref "JP5") (pin "12") (pinfunction "12_12") (pintype "passive"))
      (node (ref "K2") (pin "2") (pinfunction "2_2") (pintype "passive"))
      (node (ref "K4") (pin "2") (pinfunction "2_2") (pintype "passive"))
      (node (ref "MAIN-CON1") (pin "3") (pinfunction "3_3") (pintype "passive"))
    )
    (net (code "76") (name "RS+") (class "Default")
      (node (ref "JP2") (pin "3") (pinfunction "3_3") (pintype "passive"))
      (node (ref "JP5") (pin "3") (pinfunction "3_3") (pintype "passive"))
      (node (ref "MAIN-CON") (pin "10") (pinfunction "10_10") (pintype "passive"))
      (node (ref "MAIN-CON1") (pin "10") (pinfunction "10_10") (pintype "passive"))
    )
    (net (code "77") (name "RS-") (class "Default")
      (node (ref "JP2") (pin "4") (pinfunction "4_4") (pintype "passive"))
      (node (ref "JP5") (pin "4") (pinfunction "4_4") (pintype "passive"))
      (node (ref "MAIN-CON") (pin "9") (pinfunction "9_9") (pintype "passive"))
      (node (ref "MAIN-CON1") (pin "9") (pinfunction "9_9") (pintype "passive"))
    )
    (net (code "78") (name "TO_CHASSIS") (class "Default")
      (node (ref "GLV-G") (pin "P$1") (pinfunction "1_P$1") (pintype "passive"))
    )
    (net (code "79") (name "TS+\\") (class "Default")
      (node (ref "F10") (pin "1") (pinfunction "1_1") (pintype "passive"))
      (node (ref "F14") (pin "1") (pinfunction "1_1") (pintype "passive"))
      (node (ref "F8") (pin "1") (pinfunction "1_1") (pintype "passive"))
      (node (ref "JP3") (pin "2") (pinfunction "2_2") (pintype "passive"))
      (node (ref "JP6") (pin "2") (pinfunction "2_2") (pintype "passive"))
      (node (ref "JP8") (pin "2") (pinfunction "2_2") (pintype "passive"))
      (node (ref "K1") (pin "NO") (pinfunction "S_NO") (pintype "passive"))
      (node (ref "K2") (pin "NO") (pinfunction "S_NO") (pintype "passive"))
      (node (ref "K5") (pin "NO") (pinfunction "S_NO") (pintype "passive"))
      (node (ref "PRECHARGE") (pin "1") (pinfunction "1_1") (pintype "passive"))
      (node (ref "PRECHARGE2") (pin "1") (pinfunction "1_1") (pintype "passive"))
      (node (ref "R1") (pin "1") (pinfunction "1_1") (pintype "passive"))
      (node (ref "SR1") (pin "2") (pinfunction "2_2") (pintype "passive"))
    )
    (net (code "80") (name "TSAL+") (class "Default")
      (node (ref "JP2") (pin "6") (pinfunction "6_6") (pintype "passive"))
      (node (ref "MAIN-CON") (pin "6") (pinfunction "6_6") (pintype "passive"))
    )
    (net (code "81") (name "TSAL-") (class "Default")
      (node (ref "JP2") (pin "5") (pinfunction "5_5") (pintype "passive"))
      (node (ref "MAIN-CON") (pin "5") (pinfunction "5_5") (pintype "passive"))
    )
    (net (code "82") (name "unconnected-(BMS-Pad1)") (class "Default")
      (node (ref "BMS") (pin "1") (pinfunction "1_1") (pintype "passive"))
    )
    (net (code "83") (name "unconnected-(BMS-Pad2)") (class "Default")
      (node (ref "BMS") (pin "2") (pinfunction "2_2") (pintype "passive"))
    )
    (net (code "84") (name "unconnected-(BMS-Pad3)") (class "Default")
      (node (ref "BMS") (pin "3") (pinfunction "3_3") (pintype "passive"))
    )
    (net (code "85") (name "unconnected-(BMS-Pad4)") (class "Default")
      (node (ref "BMS") (pin "4") (pinfunction "4_4") (pintype "passive"))
    )
    (net (code "86") (name "unconnected-(BMS1-+-Pad+@1)") (class "Default")
      (node (ref "BMS1") (pin "+@1") (pinfunction "+_+@1") (pintype "passive"))
    )
    (net (code "87") (name "unconnected-(BMS2-+-Pad+@1)") (class "Default")
      (node (ref "BMS2") (pin "+@1") (pinfunction "+_+@1") (pintype "passive"))
    )
    (net (code "88") (name "unconnected-(BMS3-+-Pad+@1)") (class "Default")
      (node (ref "BMS3") (pin "+@1") (pinfunction "+_+@1") (pintype "passive"))
    )
    (net (code "89") (name "unconnected-(BMS4-+-Pad+@1)") (class "Default")
      (node (ref "BMS4") (pin "+@1") (pinfunction "+_+@1") (pintype "passive"))
    )
    (net (code "90") (name "unconnected-(BMS5-+-Pad+@1)") (class "Default")
      (node (ref "BMS5") (pin "+@1") (pinfunction "+_+@1") (pintype "passive"))
    )
    (net (code "91") (name "unconnected-(BMS6-+-Pad+@1)") (class "Default")
      (node (ref "BMS6") (pin "+@1") (pinfunction "+_+@1") (pintype "passive"))
    )
    (net (code "92") (name "unconnected-(BMS7-+-Pad+@1)") (class "Default")
      (node (ref "BMS7") (pin "+@1") (pinfunction "+_+@1") (pintype "passive"))
    )
    (net (code "93") (name "unconnected-(BMS8-+-Pad+@1)") (class "Default")
      (node (ref "BMS8") (pin "+@1") (pinfunction "+_+@1") (pintype "passive"))
    )
    (net (code "94") (name "unconnected-(BMS9-+-Pad+@1)") (class "Default")
      (node (ref "BMS9") (pin "+@1") (pinfunction "+_+@1") (pintype "passive"))
    )
    (net (code "95") (name "unconnected-(BMS10-+-Pad+@1)") (class "Default")
      (node (ref "BMS10") (pin "+@1") (pinfunction "+_+@1") (pintype "passive"))
    )
    (net (code "96") (name "unconnected-(BMS11-+-Pad+@1)") (class "Default")
      (node (ref "BMS11") (pin "+@1") (pinfunction "+_+@1") (pintype "passive"))
    )
    (net (code "97") (name "unconnected-(BMS12-+-Pad+@1)") (class "Default")
      (node (ref "BMS12") (pin "+@1") (pinfunction "+_+@1") (pintype "passive"))
    )
    (net (code "98") (name "unconnected-(BMS13-+-Pad+@1)") (class "Default")
      (node (ref "BMS13") (pin "+@1") (pinfunction "+_+@1") (pintype "passive"))
    )
    (net (code "99") (name "unconnected-(BMS14-+-Pad+@1)") (class "Default")
      (node (ref "BMS14") (pin "+@1") (pinfunction "+_+@1") (pintype "passive"))
    )
    (net (code "100") (name "unconnected-(BMS15-Pad1)") (class "Default")
      (node (ref "BMS15") (pin "1") (pinfunction "1_1") (pintype "passive"))
    )
    (net (code "101") (name "unconnected-(BMS15-Pad2)") (class "Default")
      (node (ref "BMS15") (pin "2") (pinfunction "2_2") (pintype "passive"))
    )
    (net (code "102") (name "unconnected-(BMS15-Pad3)") (class "Default")
      (node (ref "BMS15") (pin "3") (pinfunction "3_3") (pintype "passive"))
    )
    (net (code "103") (name "unconnected-(BMS15-Pad4)") (class "Default")
      (node (ref "BMS15") (pin "4") (pinfunction "4_4") (pintype "passive"))
    )
    (net (code "104") (name "unconnected-(BMS16-+-Pad+@1)") (class "Default")
      (node (ref "BMS16") (pin "+@1") (pinfunction "+_+@1") (pintype "passive"))
    )
    (net (code "105") (name "unconnected-(BMS17-+-Pad+@1)") (class "Default")
      (node (ref "BMS17") (pin "+@1") (pinfunction "+_+@1") (pintype "passive"))
    )
    (net (code "106") (name "unconnected-(BMS18-+-Pad+@1)") (class "Default")
      (node (ref "BMS18") (pin "+@1") (pinfunction "+_+@1") (pintype "passive"))
    )
    (net (code "107") (name "unconnected-(BMS19-+-Pad+@1)") (class "Default")
      (node (ref "BMS19") (pin "+@1") (pinfunction "+_+@1") (pintype "passive"))
    )
    (net (code "108") (name "unconnected-(BMS20-+-Pad+@1)") (class "Default")
      (node (ref "BMS20") (pin "+@1") (pinfunction "+_+@1") (pintype "passive"))
    )
    (net (code "109") (name "unconnected-(BMS21-+-Pad+@1)") (class "Default")
      (node (ref "BMS21") (pin "+@1") (pinfunction "+_+@1") (pintype "passive"))
    )
    (net (code "110") (name "unconnected-(BMS22-+-Pad+@1)") (class "Default")
      (node (ref "BMS22") (pin "+@1") (pinfunction "+_+@1") (pintype "passive"))
    )
    (net (code "111") (name "unconnected-(JP2-Pad13)") (class "Default")
      (node (ref "JP2") (pin "13") (pinfunction "13_13") (pintype "passive"))
    )
    (net (code "112") (name "unconnected-(JP2-Pad14)") (class "Default")
      (node (ref "JP2") (pin "14") (pinfunction "14_14") (pintype "passive"))
    )
    (net (code "113") (name "unconnected-(JP2-Pad15)") (class "Default")
      (node (ref "JP2") (pin "15") (pinfunction "15_15") (pintype "passive"))
    )
    (net (code "114") (name "unconnected-(JP2-Pad16)") (class "Default")
      (node (ref "JP2") (pin "16") (pinfunction "16_16") (pintype "passive"))
    )
    (net (code "115") (name "unconnected-(JP2-Pad17)") (class "Default")
      (node (ref "JP2") (pin "17") (pinfunction "17_17") (pintype "passive"))
    )
    (net (code "116") (name "unconnected-(JP2-Pad18)") (class "Default")
      (node (ref "JP2") (pin "18") (pinfunction "18_18") (pintype "passive"))
    )
    (net (code "117") (name "unconnected-(JP2-Pad19)") (class "Default")
      (node (ref "JP2") (pin "19") (pinfunction "19_19") (pintype "passive"))
    )
    (net (code "118") (name "unconnected-(JP2-Pad20)") (class "Default")
      (node (ref "JP2") (pin "20") (pinfunction "20_20") (pintype "passive"))
    )
    (net (code "119") (name "unconnected-(JP5-Pad5)") (class "Default")
      (node (ref "JP5") (pin "5") (pinfunction "5_5") (pintype "passive"))
    )
    (net (code "120") (name "unconnected-(JP5-Pad6)") (class "Default")
      (node (ref "JP5") (pin "6") (pinfunction "6_6") (pintype "passive"))
    )
    (net (code "121") (name "unconnected-(JP5-Pad13)") (class "Default")
      (node (ref "JP5") (pin "13") (pinfunction "13_13") (pintype "passive"))
    )
    (net (code "122") (name "unconnected-(JP5-Pad14)") (class "Default")
      (node (ref "JP5") (pin "14") (pinfunction "14_14") (pintype "passive"))
    )
    (net (code "123") (name "unconnected-(JP5-Pad15)") (class "Default")
      (node (ref "JP5") (pin "15") (pinfunction "15_15") (pintype "passive"))
    )
    (net (code "124") (name "unconnected-(JP5-Pad16)") (class "Default")
      (node (ref "JP5") (pin "16") (pinfunction "16_16") (pintype "passive"))
    )
    (net (code "125") (name "unconnected-(JP5-Pad17)") (class "Default")
      (node (ref "JP5") (pin "17") (pinfunction "17_17") (pintype "passive"))
    )
    (net (code "126") (name "unconnected-(JP5-Pad18)") (class "Default")
      (node (ref "JP5") (pin "18") (pinfunction "18_18") (pintype "passive"))
    )
    (net (code "127") (name "unconnected-(JP5-Pad19)") (class "Default")
      (node (ref "JP5") (pin "19") (pinfunction "19_19") (pintype "passive"))
    )
    (net (code "128") (name "unconnected-(JP5-Pad20)") (class "Default")
      (node (ref "JP5") (pin "20") (pinfunction "20_20") (pintype "passive"))
    )
    (net (code "129") (name "unconnected-(MAIN-CON-Pad1)") (class "Default")
      (node (ref "MAIN-CON") (pin "1") (pinfunction "1_1") (pintype "passive"))
    )
    (net (code "130") (name "unconnected-(MAIN-CON1-Pad5)") (class "Default")
      (node (ref "MAIN-CON1") (pin "5") (pinfunction "5_5") (pintype "passive"))
    )
    (net (code "131") (name "unconnected-(MAIN-CON1-Pad6)") (class "Default")
      (node (ref "MAIN-CON1") (pin "6") (pinfunction "6_6") (pintype "passive"))
    )
    (net (code "132") (name "unconnected-(U$1-DATA-HIGH-PadP$5)") (class "Default")
      (node (ref "U$1") (pin "P$5") (pinfunction "DATA-HIGH_P$5") (pintype "bidirectional"))
    )
    (net (code "133") (name "unconnected-(U$1-DATA-LOW-PadP$6)") (class "Default")
      (node (ref "U$1") (pin "P$6") (pinfunction "DATA-LOW_P$6") (pintype "bidirectional"))
    )
  )
)
